# TinyRGBSignEdge.net
KiCad netlist of a schematic drawn in EAGLE
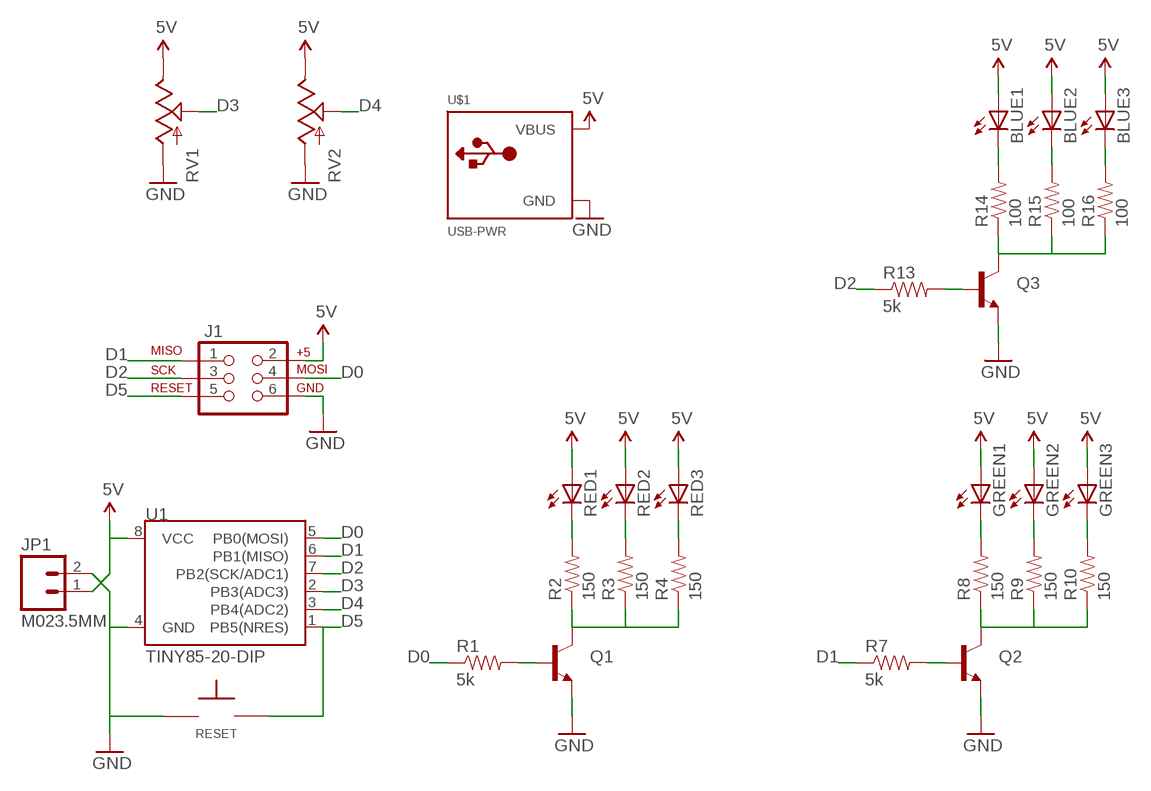
[diagram p0: schematic, sheet 1]

(export (version "E")
  (design (tool "Eeschema 10.0.6"))
  (components
    (comp (ref "BLUE1")
      (value "LED5MM")
      (footprint "eagle-import:LED5MM")
      (libsource (lib "eagle-import") (part "LED5MM"))
    )
    (comp (ref "BLUE2")
      (value "LED5MM")
      (footprint "eagle-import:LED5MM")
      (libsource (lib "eagle-import") (part "LED5MM"))
    )
    (comp (ref "BLUE3")
      (value "LED5MM")
      (footprint "eagle-import:LED5MM")
      (libsource (lib "eagle-import") (part "LED5MM"))
    )
    (comp (ref "GREEN1")
      (value "LED5MM")
      (footprint "eagle-import:LED5MM")
      (libsource (lib "eagle-import") (part "LED5MM"))
    )
    (comp (ref "GREEN2")
      (value "LED5MM")
      (footprint "eagle-import:LED5MM")
      (libsource (lib "eagle-import") (part "LED5MM"))
    )
    (comp (ref "GREEN3")
      (value "LED5MM")
      (footprint "eagle-import:LED5MM")
      (libsource (lib "eagle-import") (part "LED5MM"))
    )
    (comp (ref "J1")
      (value "AVR_SPI_PRG_6PTH")
      (footprint "eagle-import:2X3")
      (libsource (lib "eagle-import") (part "AVR_SPI_PRG_6PTH"))
    )
    (comp (ref "JP1")
      (value "M023.5MM")
      (footprint "eagle-import:SCREWTERMINAL-3.5MM-2")
      (libsource (lib "eagle-import") (part "M023.5MM"))
    )
    (comp (ref "Q1")
      (value "TRANSISTOR_NPNTO-92-AMMO")
      (footprint "eagle-import:TO-92-AMMO")
      (libsource (lib "eagle-import") (part "TRANSISTOR_NPNTO-92-AMMO"))
    )
    (comp (ref "Q2")
      (value "TRANSISTOR_NPNTO-92-AMMO")
      (footprint "eagle-import:TO-92-AMMO")
      (libsource (lib "eagle-import") (part "TRANSISTOR_NPNTO-92-AMMO"))
    )
    (comp (ref "Q3")
      (value "TRANSISTOR_NPNTO-92-AMMO")
      (footprint "eagle-import:TO-92-AMMO")
      (libsource (lib "eagle-import") (part "TRANSISTOR_NPNTO-92-AMMO"))
    )
    (comp (ref "R1")
      (value "5k")
      (footprint "eagle-import:AXIAL-0.3")
      (libsource (lib "eagle-import") (part "RESISTORAXIAL-0.3"))
    )
    (comp (ref "R2")
      (value "150")
      (footprint "eagle-import:AXIAL-0.3")
      (libsource (lib "eagle-import") (part "RESISTORAXIAL-0.3"))
    )
    (comp (ref "R3")
      (value "150")
      (footprint "eagle-import:AXIAL-0.3")
      (libsource (lib "eagle-import") (part "RESISTORAXIAL-0.3"))
    )
    (comp (ref "R4")
      (value "150")
      (footprint "eagle-import:AXIAL-0.3")
      (libsource (lib "eagle-import") (part "RESISTORAXIAL-0.3"))
    )
    (comp (ref "R7")
      (value "5k")
      (footprint "eagle-import:AXIAL-0.3")
      (libsource (lib "eagle-import") (part "RESISTORAXIAL-0.3"))
    )
    (comp (ref "R8")
      (value "150")
      (footprint "eagle-import:AXIAL-0.3")
      (libsource (lib "eagle-import") (part "RESISTORAXIAL-0.3"))
    )
    (comp (ref "R9")
      (value "150")
      (footprint "eagle-import:AXIAL-0.3")
      (libsource (lib "eagle-import") (part "RESISTORAXIAL-0.3"))
    )
    (comp (ref "R10")
      (value "150")
      (footprint "eagle-import:AXIAL-0.3")
      (libsource (lib "eagle-import") (part "RESISTORAXIAL-0.3"))
    )
    (comp (ref "R13")
      (value "5k")
      (footprint "eagle-import:AXIAL-0.3")
      (libsource (lib "eagle-import") (part "RESISTORAXIAL-0.3"))
    )
    (comp (ref "R14")
      (value "100")
      (footprint "eagle-import:AXIAL-0.3")
      (libsource (lib "eagle-import") (part "RESISTORAXIAL-0.3"))
    )
    (comp (ref "R15")
      (value "100")
      (footprint "eagle-import:AXIAL-0.3")
      (libsource (lib "eagle-import") (part "RESISTORAXIAL-0.3"))
    )
    (comp (ref "R16")
      (value "100")
      (footprint "eagle-import:AXIAL-0.3")
      (libsource (lib "eagle-import") (part "RESISTORAXIAL-0.3"))
    )
    (comp (ref "RED1")
      (value "LED5MM")
      (footprint "eagle-import:LED5MM")
      (libsource (lib "eagle-import") (part "LED5MM"))
    )
    (comp (ref "RED2")
      (value "LED5MM")
      (footprint "eagle-import:LED5MM")
      (libsource (lib "eagle-import") (part "LED5MM"))
    )
    (comp (ref "RED3")
      (value "LED5MM")
      (footprint "eagle-import:LED5MM")
      (libsource (lib "eagle-import") (part "LED5MM"))
    )
    (comp (ref "RESET")
      (value "TAC_SPST_NO")
      (footprint "eagle-import:TAC_SPST_NO")
      (libsource (lib "eagle-import") (part "TAC_SPST_NO"))
    )
    (comp (ref "RV1")
      (value "POTTRIM")
      (footprint "eagle-import:TRIM_POT")
      (libsource (lib "eagle-import") (part "POTTRIM"))
    )
    (comp (ref "RV2")
      (value "POTTRIM")
      (footprint "eagle-import:TRIM_POT")
      (libsource (lib "eagle-import") (part "POTTRIM"))
    )
    (comp (ref "U$1")
      (value "USB-PWR")
      (footprint "eagle-import:USB-MINIB-THM-MOLEX-PWRONLY")
      (libsource (lib "eagle-import") (part "USB-PWR"))
    )
    (comp (ref "U1")
      (value "TINY85-20-DIP")
      (footprint "eagle-import:DIP08")
      (libsource (lib "eagle-import") (part "ATTINY45TINY85-20-DIP"))
    )
  )
  (nets
    (net (code "1") (name "/D0") (class "Default")
      (node (ref "J1") (pin "4") (pinfunction "4_4") (pintype "passive"))
      (node (ref "R1") (pin "P$1") (pinfunction "1_P$1") (pintype "passive"))
      (node (ref "U1") (pin "5") (pinfunction "PB0(MOSI)_5") (pintype "bidirectional"))
    )
    (net (code "2") (name "/D1") (class "Default")
      (node (ref "J1") (pin "1") (pinfunction "1_1") (pintype "passive"))
      (node (ref "R7") (pin "P$1") (pinfunction "1_P$1") (pintype "passive"))
      (node (ref "U1") (pin "6") (pinfunction "PB1(MISO)_6") (pintype "bidirectional"))
    )
    (net (code "3") (name "/D2") (class "Default")
      (node (ref "J1") (pin "3") (pinfunction "3_3") (pintype "passive"))
      (node (ref "R13") (pin "P$1") (pinfunction "1_P$1") (pintype "passive"))
      (node (ref "U1") (pin "7") (pinfunction "PB2(SCK/ADC1)_7") (pintype "bidirectional"))
    )
    (net (code "4") (name "/D3") (class "Default")
      (node (ref "RV1") (pin "1") (pinfunction "S_1") (pintype "passive"))
      (node (ref "U1") (pin "2") (pinfunction "PB3(ADC3)_2") (pintype "bidirectional"))
    )
    (net (code "5") (name "/D4") (class "Default")
      (node (ref "RV2") (pin "1") (pinfunction "S_1") (pintype "passive"))
      (node (ref "U1") (pin "3") (pinfunction "PB4(ADC2)_3") (pintype "bidirectional"))
    )
    (net (code "6") (name "/D5") (class "Default")
      (node (ref "J1") (pin "5") (pinfunction "5_5") (pintype "passive"))
      (node (ref "RESET") (pin "P$2") (pinfunction "P$2_P$2") (pintype "bidirectional"))
      (node (ref "U1") (pin "1") (pinfunction "PB5(NRES)_1") (pintype "bidirectional"))
    )
    (net (code "7") (name "5V") (class "Default")
      (node (ref "BLUE1") (pin "A") (pinfunction "A_A") (pintype "passive"))
      (node (ref "BLUE2") (pin "A") (pinfunction "A_A") (pintype "passive"))
      (node (ref "BLUE3") (pin "A") (pinfunction "A_A") (pintype "passive"))
      (node (ref "GREEN1") (pin "A") (pinfunction "A_A") (pintype "passive"))
      (node (ref "GREEN2") (pin "A") (pinfunction "A_A") (pintype "passive"))
      (node (ref "GREEN3") (pin "A") (pinfunction "A_A") (pintype "passive"))
      (node (ref "J1") (pin "2") (pinfunction "2_2") (pintype "passive"))
      (node (ref "JP1") (pin "1") (pinfunction "1_1") (pintype "passive"))
      (node (ref "RED1") (pin "A") (pinfunction "A_A") (pintype "passive"))
      (node (ref "RED2") (pin "A") (pinfunction "A_A") (pintype "passive"))
      (node (ref "RED3") (pin "A") (pinfunction "A_A") (pintype "passive"))
      (node (ref "RV1") (pin "2") (pinfunction "E_2") (pintype "passive"))
      (node (ref "RV2") (pin "2") (pinfunction "E_2") (pintype "passive"))
      (node (ref "U$1") (pin "VBUS") (pinfunction "VBUS_VBUS") (pintype "power_in"))
      (node (ref "U1") (pin "8") (pinfunction "VCC_8") (pintype "bidirectional"))
    )
    (net (code "8") (name "GND") (class "Default")
      (node (ref "J1") (pin "6") (pinfunction "6_6") (pintype "passive"))
      (node (ref "JP1") (pin "2") (pinfunction "2_2") (pintype "passive"))
      (node (ref "Q1") (pin "1") (pinfunction "E_1") (pintype "passive"))
      (node (ref "Q2") (pin "1") (pinfunction "E_1") (pintype "passive"))
      (node (ref "Q3") (pin "1") (pinfunction "E_1") (pintype "passive"))
      (node (ref "RESET") (pin "P$1") (pinfunction "P$1_P$1") (pintype "bidirectional"))
      (node (ref "RV1") (pin "3") (pinfunction "A_3") (pintype "passive"))
      (node (ref "RV2") (pin "3") (pinfunction "A_3") (pintype "passive"))
      (node (ref "U$1") (pin "GND") (pinfunction "GND_GND") (pintype "power_in"))
      (node (ref "U1") (pin "4") (pinfunction "GND_4") (pintype "bidirectional"))
    )
    (net (code "9") (name "Net-(BLUE1-C)") (class "Default")
      (node (ref "BLUE1") (pin "K") (pinfunction "C_K") (pintype "passive"))
      (node (ref "R14") (pin "P$2") (pinfunction "2_P$2") (pintype "passive"))
    )
    (net (code "10") (name "Net-(BLUE2-C)") (class "Default")
      (node (ref "BLUE2") (pin "K") (pinfunction "C_K") (pintype "passive"))
      (node (ref "R15") (pin "P$2") (pinfunction "2_P$2") (pintype "passive"))
    )
    (net (code "11") (name "Net-(BLUE3-C)") (class "Default")
      (node (ref "BLUE3") (pin "K") (pinfunction "C_K") (pintype "passive"))
      (node (ref "R16") (pin "P$2") (pinfunction "2_P$2") (pintype "passive"))
    )
    (net (code "12") (name "Net-(GREEN1-C)") (class "Default")
      (node (ref "GREEN1") (pin "K") (pinfunction "C_K") (pintype "passive"))
      (node (ref "R8") (pin "P$2") (pinfunction "2_P$2") (pintype "passive"))
    )
    (net (code "13") (name "Net-(GREEN2-C)") (class "Default")
      (node (ref "GREEN2") (pin "K") (pinfunction "C_K") (pintype "passive"))
      (node (ref "R9") (pin "P$2") (pinfunction "2_P$2") (pintype "passive"))
    )
    (net (code "14") (name "Net-(GREEN3-C)") (class "Default")
      (node (ref "GREEN3") (pin "K") (pinfunction "C_K") (pintype "passive"))
      (node (ref "R10") (pin "P$2") (pinfunction "2_P$2") (pintype "passive"))
    )
    (net (code "15") (name "Net-(Q1-B)") (class "Default")
      (node (ref "Q1") (pin "2") (pinfunction "B_2") (pintype "passive"))
      (node (ref "R1") (pin "P$2") (pinfunction "2_P$2") (pintype "passive"))
    )
    (net (code "16") (name "Net-(Q1-C)") (class "Default")
      (node (ref "Q1") (pin "3") (pinfunction "C_3") (pintype "passive"))
      (node (ref "R2") (pin "P$1") (pinfunction "1_P$1") (pintype "passive"))
      (node (ref "R3") (pin "P$1") (pinfunction "1_P$1") (pintype "passive"))
      (node (ref "R4") (pin "P$1") (pinfunction "1_P$1") (pintype "passive"))
    )
    (net (code "17") (name "Net-(Q2-B)") (class "Default")
      (node (ref "Q2") (pin "2") (pinfunction "B_2") (pintype "passive"))
      (node (ref "R7") (pin "P$2") (pinfunction "2_P$2") (pintype "passive"))
    )
    (net (code "18") (name "Net-(Q2-C)") (class "Default")
      (node (ref "Q2") (pin "3") (pinfunction "C_3") (pintype "passive"))
      (node (ref "R10") (pin "P$1") (pinfunction "1_P$1") (pintype "passive"))
      (node (ref "R8") (pin "P$1") (pinfunction "1_P$1") (pintype "passive"))
      (node (ref "R9") (pin "P$1") (pinfunction "1_P$1") (pintype "passive"))
    )
    (net (code "19") (name "Net-(Q3-B)") (class "Default")
      (node (ref "Q3") (pin "2") (pinfunction "B_2") (pintype "passive"))
      (node (ref "R13") (pin "P$2") (pinfunction "2_P$2") (pintype "passive"))
    )
    (net (code "20") (name "Net-(Q3-C)") (class "Default")
      (node (ref "Q3") (pin "3") (pinfunction "C_3") (pintype "passive"))
      (node (ref "R14") (pin "P$1") (pinfunction "1_P$1") (pintype "passive"))
      (node (ref "R15") (pin "P$1") (pinfunction "1_P$1") (pintype "passive"))
      (node (ref "R16") (pin "P$1") (pinfunction "1_P$1") (pintype "passive"))
    )
    (net (code "21") (name "Net-(R2-2)") (class "Default")
      (node (ref "R2") (pin "P$2") (pinfunction "2_P$2") (pintype "passive"))
      (node (ref "RED1") (pin "K") (pinfunction "C_K") (pintype "passive"))
    )
    (net (code "22") (name "Net-(R3-2)") (class "Default")
      (node (ref "R3") (pin "P$2") (pinfunction "2_P$2") (pintype "passive"))
      (node (ref "RED2") (pin "K") (pinfunction "C_K") (pintype "passive"))
    )
    (net (code "23") (name "Net-(R4-2)") (class "Default")
      (node (ref "R4") (pin "P$2") (pinfunction "2_P$2") (pintype "passive"))
      (node (ref "RED3") (pin "K") (pinfunction "C_K") (pintype "passive"))
    )
  )
)
